# pc2_key.net
KiCad netlist of a schematic drawn in EAGLE
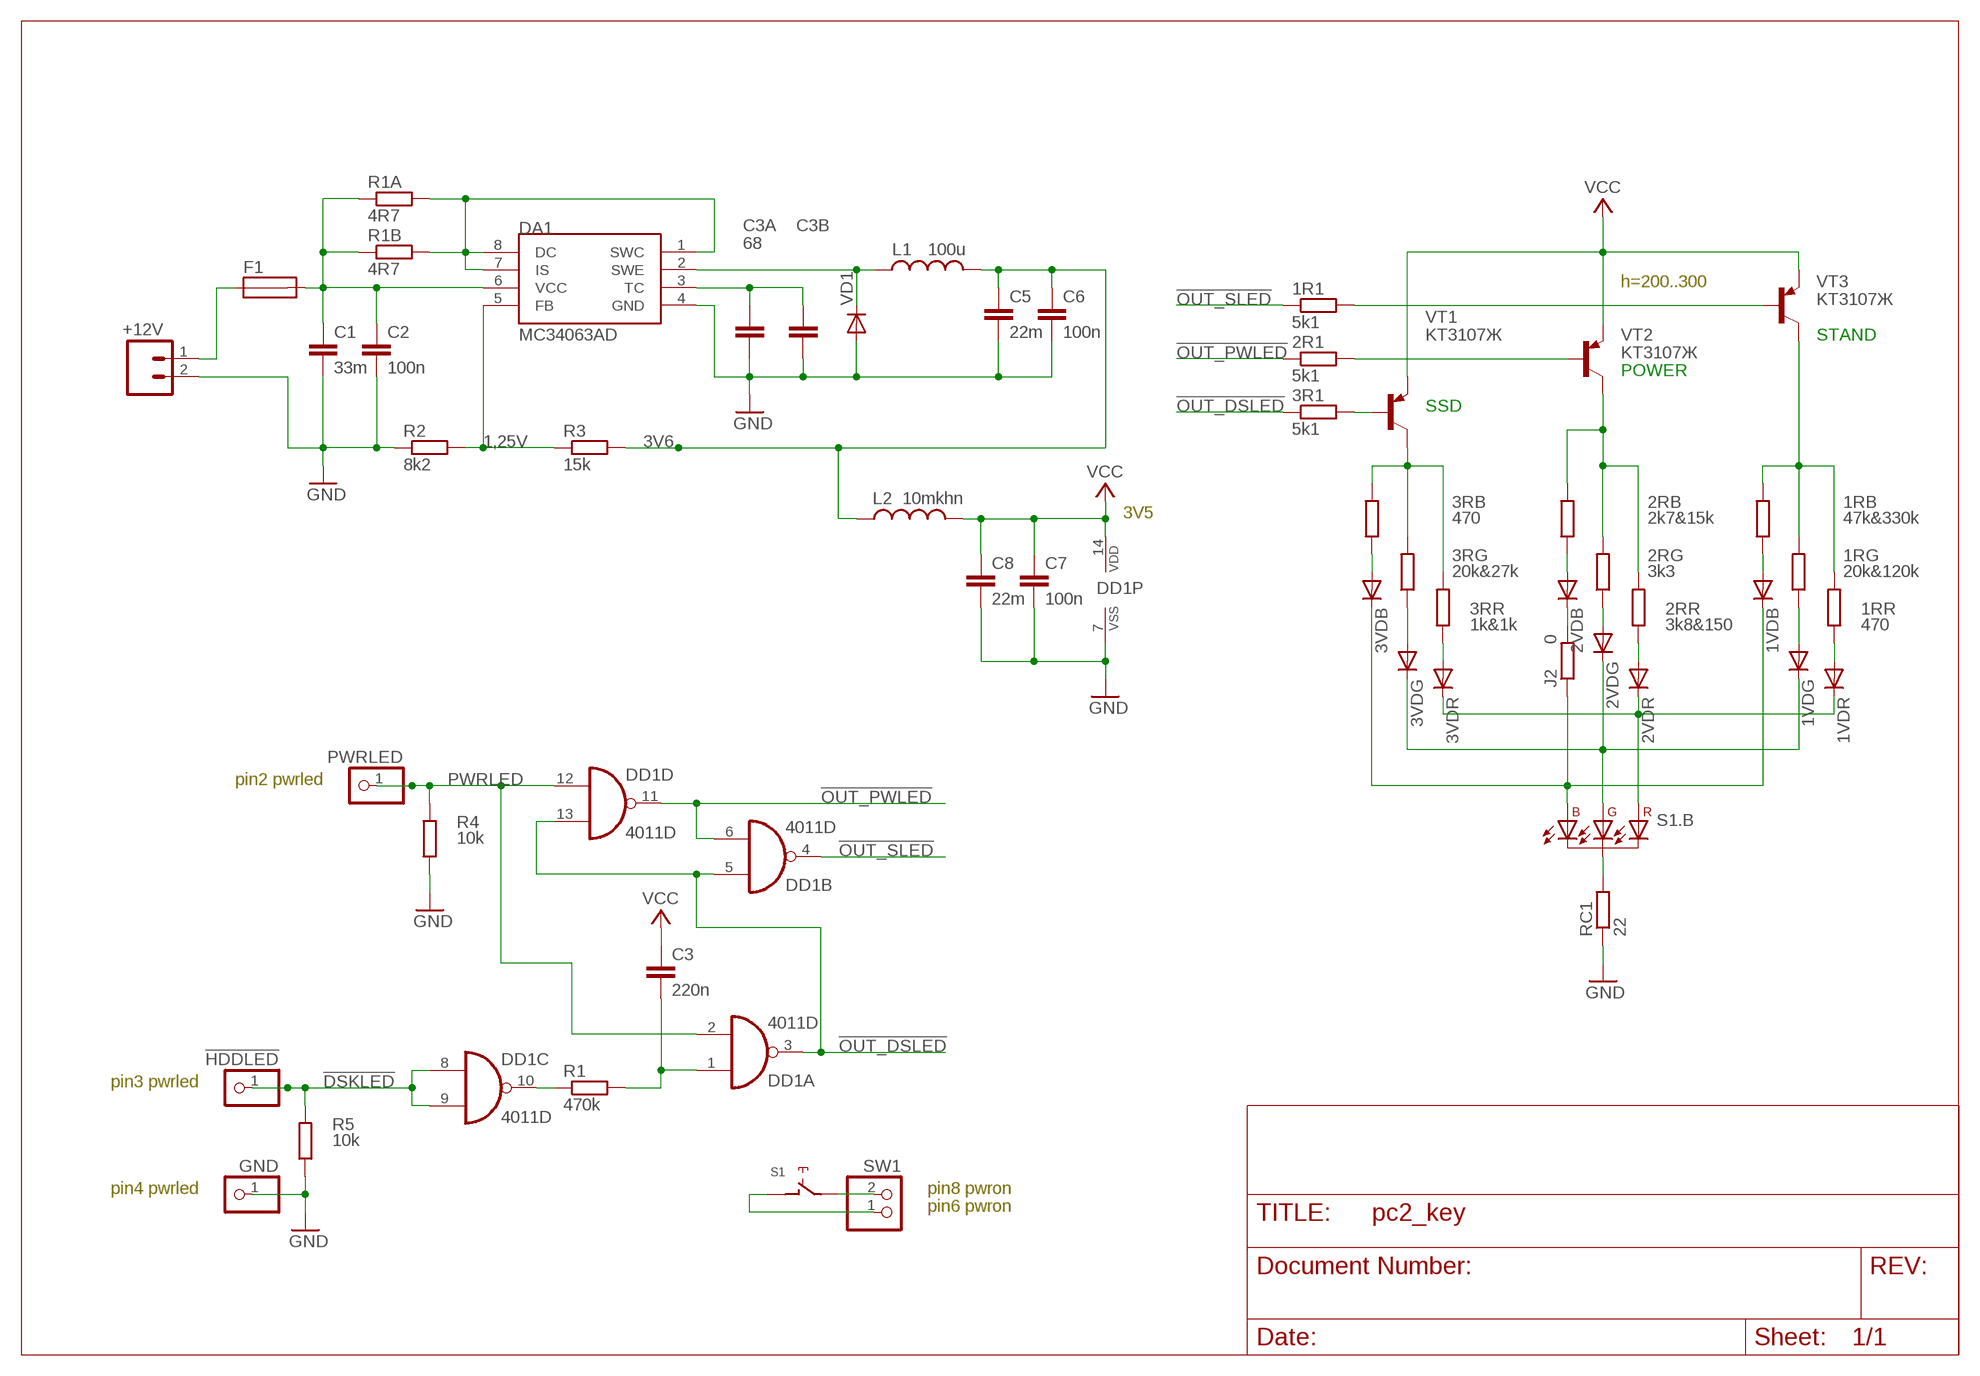
[diagram p0: schematic, sheet 1]

(export (version "E")
  (design (tool "Eeschema 10.0.6"))
  (components
    (comp (ref "!HDDLED")
      (value "PINHD-1X1")
      (footprint "eagle-import:1X01")
      (libsource (lib "eagle-import") (part "PINHD-1X1"))
    )
    (comp (ref "+12V")
      (value "CON_2P")
      (footprint "eagle-import:CON_PWR_2PIN4MM")
      (libsource (lib "eagle-import") (part "CON_2P"))
    )
    (comp (ref "1R1")
      (value "5k1")
      (footprint "eagle-import:R1206W")
      (libsource (lib "eagle-import") (part "R-EU_R1206W"))
    )
    (comp (ref "1RB")
      (value "47k&330k")
      (footprint "eagle-import:R0805")
      (libsource (lib "eagle-import") (part "R-EU_R0805"))
    )
    (comp (ref "1RG")
      (value "20k&120k")
      (footprint "eagle-import:R0805")
      (libsource (lib "eagle-import") (part "R-EU_R0805"))
    )
    (comp (ref "1RR")
      (value "470")
      (footprint "eagle-import:R0805")
      (libsource (lib "eagle-import") (part "R-EU_R0805"))
    )
    (comp (ref "1VDB")
      (value "DIODE-SOD80C")
      (footprint "eagle-import:SOD80C")
      (libsource (lib "eagle-import") (part "DIODE-SOD80C"))
    )
    (comp (ref "1VDG")
      (value "DIODE-SOD80C")
      (footprint "eagle-import:SOD80C")
      (libsource (lib "eagle-import") (part "DIODE-SOD80C"))
    )
    (comp (ref "1VDR")
      (value "DIODE-SOD80C")
      (footprint "eagle-import:SOD80C")
      (libsource (lib "eagle-import") (part "DIODE-SOD80C"))
    )
    (comp (ref "2R1")
      (value "5k1")
      (footprint "eagle-import:R1206W")
      (libsource (lib "eagle-import") (part "R-EU_R1206W"))
    )
    (comp (ref "2RB")
      (value "2k7&15k")
      (footprint "eagle-import:R0805")
      (libsource (lib "eagle-import") (part "R-EU_R0805"))
    )
    (comp (ref "2RG")
      (value "3k3")
      (footprint "eagle-import:R0805")
      (libsource (lib "eagle-import") (part "R-EU_R0805"))
    )
    (comp (ref "2RR")
      (value "3k8&150")
      (footprint "eagle-import:R0805")
      (libsource (lib "eagle-import") (part "R-EU_R0805"))
    )
    (comp (ref "2VDB")
      (value "DIODE-SOD80C")
      (footprint "eagle-import:SOD80C")
      (libsource (lib "eagle-import") (part "DIODE-SOD80C"))
    )
    (comp (ref "2VDG")
      (value "DIODE-SOD80C")
      (footprint "eagle-import:SOD80C")
      (libsource (lib "eagle-import") (part "DIODE-SOD80C"))
    )
    (comp (ref "2VDR")
      (value "DIODE-SOD80C")
      (footprint "eagle-import:SOD80C")
      (libsource (lib "eagle-import") (part "DIODE-SOD80C"))
    )
    (comp (ref "3R1")
      (value "5k1")
      (footprint "eagle-import:R1206W")
      (libsource (lib "eagle-import") (part "R-EU_R1206W"))
    )
    (comp (ref "3RB")
      (value "470")
      (footprint "eagle-import:R0805")
      (libsource (lib "eagle-import") (part "R-EU_R0805"))
    )
    (comp (ref "3RG")
      (value "20k&27k")
      (footprint "eagle-import:R0805")
      (libsource (lib "eagle-import") (part "R-EU_R0805"))
    )
    (comp (ref "3RR")
      (value "1k&1k")
      (footprint "eagle-import:R0805")
      (libsource (lib "eagle-import") (part "R-EU_R0805"))
    )
    (comp (ref "3VDB")
      (value "DIODE-SOD80C")
      (footprint "eagle-import:SOD80C")
      (libsource (lib "eagle-import") (part "DIODE-SOD80C"))
    )
    (comp (ref "3VDG")
      (value "DIODE-SOD80C")
      (footprint "eagle-import:SOD80C")
      (libsource (lib "eagle-import") (part "DIODE-SOD80C"))
    )
    (comp (ref "3VDR")
      (value "DIODE-SOD80C")
      (footprint "eagle-import:SOD80C")
      (libsource (lib "eagle-import") (part "DIODE-SOD80C"))
    )
    (comp (ref "C1")
      (value "33m")
      (footprint "eagle-import:C1210")
      (libsource (lib "eagle-import") (part "C-EUC1210"))
    )
    (comp (ref "C2")
      (value "100n")
      (footprint "eagle-import:C0805K")
      (libsource (lib "eagle-import") (part "resistor_C-EUC0805K"))
    )
    (comp (ref "C3")
      (value "220n")
      (footprint "eagle-import:C0805")
      (libsource (lib "eagle-import") (part "resistor_C-EUC0805"))
    )
    (comp (ref "C3A")
      (value "68")
      (footprint "eagle-import:C0805K")
      (libsource (lib "eagle-import") (part "resistor_C-EUC0805K"))
    )
    (comp (ref "C3B")
      (value "C-EUC0805K")
      (footprint "eagle-import:C0805K")
      (libsource (lib "eagle-import") (part "resistor_C-EUC0805K"))
    )
    (comp (ref "C5")
      (value "22m")
      (footprint "eagle-import:C1210")
      (libsource (lib "eagle-import") (part "C-EUC1210"))
    )
    (comp (ref "C6")
      (value "100n")
      (footprint "eagle-import:C0805K")
      (libsource (lib "eagle-import") (part "resistor_C-EUC0805K"))
    )
    (comp (ref "C7")
      (value "100n")
      (footprint "eagle-import:C0805K")
      (libsource (lib "eagle-import") (part "resistor_C-EUC0805K"))
    )
    (comp (ref "C8")
      (value "22m")
      (footprint "eagle-import:C1210")
      (libsource (lib "eagle-import") (part "C-EUC1210"))
    )
    (comp (ref "DA1")
      (value "MC34063AD")
      (footprint "eagle-import:SOIC8")
      (libsource (lib "eagle-import") (part "MC34063AD"))
    )
    (comp (ref "DD1")
      (value "4011D")
      (footprint "eagle-import:SO14")
      (libsource (lib "eagle-import") (part "4011D"))
    )
    (comp (ref "F1")
      (value "SH32")
      (footprint "eagle-import:SH32")
      (fields (field (name "MPN") "10207101009"))
      (libsource (lib "eagle-import") (part "SH32"))
    )
    (comp (ref "GND")
      (value "PINHD-1X1")
      (footprint "eagle-import:1X01")
      (libsource (lib "eagle-import") (part "PINHD-1X1"))
    )
    (comp (ref "J2")
      (value "0")
      (footprint "eagle-import:R1206W")
      (libsource (lib "eagle-import") (part "R-EU_R1206W"))
    )
    (comp (ref "L1")
      (value "100u")
      (footprint "eagle-import:LH7X10MM")
      (libsource (lib "eagle-import") (part "L_LH7X10MM"))
    )
    (comp (ref "L2")
      (value "10mkhn")
      (footprint "eagle-import:PIS2816")
      (libsource (lib "eagle-import") (part "L-USPIS2816"))
    )
    (comp (ref "PWRLED")
      (value "PINHD-1X1")
      (footprint "eagle-import:1X01")
      (libsource (lib "eagle-import") (part "PINHD-1X1"))
    )
    (comp (ref "R1")
      (value "470k")
      (footprint "eagle-import:M0805")
      (libsource (lib "eagle-import") (part "R-EU_M0805"))
    )
    (comp (ref "R1A")
      (value "4R7")
      (footprint "eagle-import:R1206")
      (libsource (lib "eagle-import") (part "resistor_R-EU_R1206"))
    )
    (comp (ref "R1B")
      (value "4R7")
      (footprint "eagle-import:R1206")
      (libsource (lib "eagle-import") (part "resistor_R-EU_R1206"))
    )
    (comp (ref "R2")
      (value "8k2")
      (footprint "eagle-import:R0805")
      (libsource (lib "eagle-import") (part "resistor_R-EU_R0805"))
    )
    (comp (ref "R3")
      (value "15k")
      (footprint "eagle-import:R0805")
      (libsource (lib "eagle-import") (part "resistor_R-EU_R0805"))
    )
    (comp (ref "R4")
      (value "10k")
      (footprint "eagle-import:M0805")
      (libsource (lib "eagle-import") (part "R-EU_M0805"))
    )
    (comp (ref "R5")
      (value "10k")
      (footprint "eagle-import:R1206W")
      (libsource (lib "eagle-import") (part "R-EU_R1206W"))
    )
    (comp (ref "RC1")
      (value "22")
      (footprint "eagle-import:R0805")
      (libsource (lib "eagle-import") (part "R-EU_R0805"))
    )
    (comp (ref "S1")
      (value "CHERRY-MX")
      (footprint "eagle-import:CHERRY-MX-4P")
      (libsource (lib "eagle-import") (part "CHERRY-MX"))
    )
    (comp (ref "SW1")
      (value "PINHD-1X2")
      (footprint "eagle-import:1X02")
      (libsource (lib "eagle-import") (part "PINHD-1X2"))
    )
    (comp (ref "VD1")
      (value "DIODE-SMB")
      (footprint "eagle-import:SMB")
      (libsource (lib "eagle-import") (part "DIODE-SMB"))
    )
    (comp (ref "VT1")
      (value "KT3107Ж")
      (footprint "eagle-import:TO92")
      (libsource (lib "eagle-import") (part "BJT_PNP_TO-92_EBC"))
    )
    (comp (ref "VT2")
      (value "KT3107Ж")
      (footprint "eagle-import:TO92")
      (libsource (lib "eagle-import") (part "BJT_PNP_TO-92_EBC"))
    )
    (comp (ref "VT3")
      (value "KT3107Ж")
      (footprint "eagle-import:TO92")
      (libsource (lib "eagle-import") (part "BJT_PNP_TO-92_EBC"))
    )
  )
  (nets
    (net (code "1") (name "/1,25V") (class "Default")
      (node (ref "DA1") (pin "5") (pinfunction "FB_5") (pintype "passive"))
      (node (ref "R2") (pin "2") (pinfunction "2_2") (pintype "passive"))
      (node (ref "R3") (pin "1") (pinfunction "1_1") (pintype "passive"))
    )
    (net (code "2") (name "/3V6") (class "Default")
      (node (ref "C5") (pin "1") (pinfunction "1_1") (pintype "passive"))
      (node (ref "C6") (pin "1") (pinfunction "1_1") (pintype "passive"))
      (node (ref "L1") (pin "1") (pinfunction "1_1") (pintype "passive"))
      (node (ref "L2") (pin "1") (pinfunction "1_1") (pintype "passive"))
      (node (ref "R3") (pin "2") (pinfunction "2_2") (pintype "passive"))
    )
    (net (code "3") (name "/PWRLED") (class "Default")
      (node (ref "DD1") (pin "12") (pinfunction "I0_12") (pintype "input"))
      (node (ref "DD1") (pin "2") (pinfunction "I1_2") (pintype "input"))
      (node (ref "PWRLED") (pin "1") (pinfunction "1_1") (pintype "passive"))
      (node (ref "R4") (pin "2") (pinfunction "2_2") (pintype "passive"))
    )
    (net (code "4") (name "/~{DSKLED}") (class "Default")
      (node (ref "!HDDLED") (pin "1") (pinfunction "1_1") (pintype "passive"))
      (node (ref "DD1") (pin "8") (pinfunction "I0_8") (pintype "input"))
      (node (ref "DD1") (pin "9") (pinfunction "I1_9") (pintype "input"))
      (node (ref "R5") (pin "2") (pinfunction "2_2") (pintype "passive"))
    )
    (net (code "5") (name "/~{OUT_DSLED}") (class "Default")
      (node (ref "3R1") (pin "1") (pinfunction "1_1") (pintype "passive"))
      (node (ref "DD1") (pin "13") (pinfunction "I1_13") (pintype "input"))
      (node (ref "DD1") (pin "3") (pinfunction "O_3") (pintype "output"))
      (node (ref "DD1") (pin "5") (pinfunction "I0_5") (pintype "input"))
    )
    (net (code "6") (name "/~{OUT_PWLED}") (class "Default")
      (node (ref "2R1") (pin "1") (pinfunction "1_1") (pintype "passive"))
      (node (ref "DD1") (pin "11") (pinfunction "O_11") (pintype "output"))
      (node (ref "DD1") (pin "6") (pinfunction "I1_6") (pintype "input"))
    )
    (net (code "7") (name "/~{OUT_SLED}") (class "Default")
      (node (ref "1R1") (pin "1") (pinfunction "1_1") (pintype "passive"))
      (node (ref "DD1") (pin "4") (pinfunction "O_4") (pintype "output"))
    )
    (net (code "8") (name "GND") (class "Default")
      (node (ref "+12V") (pin "2") (pinfunction "2_2") (pintype "passive"))
      (node (ref "C1") (pin "2") (pinfunction "2_2") (pintype "passive"))
      (node (ref "C2") (pin "2") (pinfunction "2_2") (pintype "passive"))
      (node (ref "C3A") (pin "2") (pinfunction "2_2") (pintype "passive"))
      (node (ref "C3B") (pin "2") (pinfunction "2_2") (pintype "passive"))
      (node (ref "C5") (pin "2") (pinfunction "2_2") (pintype "passive"))
      (node (ref "C6") (pin "2") (pinfunction "2_2") (pintype "passive"))
      (node (ref "C7") (pin "2") (pinfunction "2_2") (pintype "passive"))
      (node (ref "C8") (pin "2") (pinfunction "2_2") (pintype "passive"))
      (node (ref "DA1") (pin "4") (pinfunction "GND_4") (pintype "passive"))
      (node (ref "DD1") (pin "7") (pinfunction "VSS_7") (pintype "power_in"))
      (node (ref "GND") (pin "1") (pinfunction "1_1") (pintype "passive"))
      (node (ref "R2") (pin "1") (pinfunction "1_1") (pintype "passive"))
      (node (ref "R4") (pin "1") (pinfunction "1_1") (pintype "passive"))
      (node (ref "R5") (pin "1") (pinfunction "1_1") (pintype "passive"))
      (node (ref "RC1") (pin "1") (pinfunction "1_1") (pintype "passive"))
      (node (ref "VD1") (pin "A") (pinfunction "A_A") (pintype "passive"))
    )
    (net (code "9") (name "Net-(1RB-Pad1)") (class "Default")
      (node (ref "1RB") (pin "1") (pinfunction "1_1") (pintype "passive"))
      (node (ref "1VDB") (pin "A") (pinfunction "A_A") (pintype "passive"))
    )
    (net (code "10") (name "Net-(1RG-Pad1)") (class "Default")
      (node (ref "1RG") (pin "1") (pinfunction "1_1") (pintype "passive"))
      (node (ref "1VDG") (pin "A") (pinfunction "A_A") (pintype "passive"))
    )
    (net (code "11") (name "Net-(1RR-Pad1)") (class "Default")
      (node (ref "1RR") (pin "1") (pinfunction "1_1") (pintype "passive"))
      (node (ref "1VDR") (pin "A") (pinfunction "A_A") (pintype "passive"))
    )
    (net (code "12") (name "Net-(2RB-Pad1)") (class "Default")
      (node (ref "2RB") (pin "1") (pinfunction "1_1") (pintype "passive"))
      (node (ref "2VDB") (pin "A") (pinfunction "A_A") (pintype "passive"))
    )
    (net (code "13") (name "Net-(2RG-Pad1)") (class "Default")
      (node (ref "2RG") (pin "1") (pinfunction "1_1") (pintype "passive"))
      (node (ref "2VDG") (pin "A") (pinfunction "A_A") (pintype "passive"))
    )
    (net (code "14") (name "Net-(2RR-Pad1)") (class "Default")
      (node (ref "2RR") (pin "1") (pinfunction "1_1") (pintype "passive"))
      (node (ref "2VDR") (pin "A") (pinfunction "A_A") (pintype "passive"))
    )
    (net (code "15") (name "Net-(2VDB-PadC)") (class "Default")
      (node (ref "2VDB") (pin "C") (pinfunction "C_C") (pintype "passive"))
      (node (ref "J2") (pin "2") (pinfunction "2_2") (pintype "passive"))
    )
    (net (code "16") (name "Net-(3RB-Pad1)") (class "Default")
      (node (ref "3RB") (pin "1") (pinfunction "1_1") (pintype "passive"))
      (node (ref "3VDB") (pin "A") (pinfunction "A_A") (pintype "passive"))
    )
    (net (code "17") (name "Net-(3RG-Pad1)") (class "Default")
      (node (ref "3RG") (pin "1") (pinfunction "1_1") (pintype "passive"))
      (node (ref "3VDG") (pin "A") (pinfunction "A_A") (pintype "passive"))
    )
    (net (code "18") (name "Net-(3RR-Pad1)") (class "Default")
      (node (ref "3RR") (pin "1") (pinfunction "1_1") (pintype "passive"))
      (node (ref "3VDR") (pin "A") (pinfunction "A_A") (pintype "passive"))
    )
    (net (code "19") (name "Net-(DA1-DC)") (class "Default")
      (node (ref "DA1") (pin "1") (pinfunction "SWC_1") (pintype "passive"))
      (node (ref "DA1") (pin "7") (pinfunction "IS_7") (pintype "passive"))
      (node (ref "DA1") (pin "8") (pinfunction "DC_8") (pintype "passive"))
      (node (ref "R1A") (pin "2") (pinfunction "2_2") (pintype "passive"))
      (node (ref "R1B") (pin "2") (pinfunction "2_2") (pintype "passive"))
    )
    (net (code "20") (name "Net-(DA1-SWE)") (class "Default")
      (node (ref "DA1") (pin "2") (pinfunction "SWE_2") (pintype "passive"))
      (node (ref "L1") (pin "2") (pinfunction "2_2") (pintype "passive"))
      (node (ref "VD1") (pin "C") (pinfunction "C_C") (pintype "passive"))
    )
    (net (code "21") (name "Net-(DA1-TC)") (class "Default")
      (node (ref "C3A") (pin "1") (pinfunction "1_1") (pintype "passive"))
      (node (ref "C3B") (pin "1") (pinfunction "1_1") (pintype "passive"))
      (node (ref "DA1") (pin "3") (pinfunction "TC_3") (pintype "passive"))
    )
    (net (code "22") (name "Net-(DA1-VCC)") (class "Default")
      (node (ref "C1") (pin "1") (pinfunction "1_1") (pintype "passive"))
      (node (ref "C2") (pin "1") (pinfunction "1_1") (pintype "passive"))
      (node (ref "DA1") (pin "6") (pinfunction "VCC_6") (pintype "passive"))
      (node (ref "F1") (pin "P$2") (pinfunction "2A_P$2") (pintype "passive"))
      (node (ref "R1A") (pin "1") (pinfunction "1_1") (pintype "passive"))
      (node (ref "R1B") (pin "1") (pinfunction "1_1") (pintype "passive"))
    )
    (net (code "23") (name "Net-(DD1A-I0)") (class "Default")
      (node (ref "C3") (pin "2") (pinfunction "2_2") (pintype "passive"))
      (node (ref "DD1") (pin "1") (pinfunction "I0_1") (pintype "input"))
      (node (ref "R1") (pin "2") (pinfunction "2_2") (pintype "passive"))
    )
    (net (code "24") (name "Net-(DD1C-O)") (class "Default")
      (node (ref "DD1") (pin "10") (pinfunction "O_10") (pintype "output"))
      (node (ref "R1") (pin "1") (pinfunction "1_1") (pintype "passive"))
    )
    (net (code "25") (name "Net-(F1-1A)") (class "Default")
      (node (ref "+12V") (pin "1") (pinfunction "1_1") (pintype "passive"))
      (node (ref "F1") (pin "P$1") (pinfunction "1A_P$1") (pintype "passive"))
    )
    (net (code "26") (name "Net-(S1-PadSW1)") (class "Default")
      (node (ref "S1") (pin "SW1") (pinfunction "SW1_SW1") (pintype "passive"))
      (node (ref "SW1") (pin "2") (pinfunction "2_2") (pintype "passive"))
    )
    (net (code "27") (name "Net-(S1-PadSW2)") (class "Default")
      (node (ref "S1") (pin "SW2") (pinfunction "SW2_SW2") (pintype "passive"))
      (node (ref "SW1") (pin "1") (pinfunction "1_1") (pintype "passive"))
    )
    (net (code "28") (name "Net-(S1B-B)") (class "Default")
      (node (ref "1VDB") (pin "C") (pinfunction "C_C") (pintype "passive"))
      (node (ref "3VDB") (pin "C") (pinfunction "C_C") (pintype "passive"))
      (node (ref "J2") (pin "1") (pinfunction "1_1") (pintype "passive"))
      (node (ref "S1") (pin "D1") (pinfunction "B_D1") (pintype "passive"))
    )
    (net (code "29") (name "Net-(S1B-G)") (class "Default")
      (node (ref "1VDG") (pin "C") (pinfunction "C_C") (pintype "passive"))
      (node (ref "2VDG") (pin "C") (pinfunction "C_C") (pintype "passive"))
      (node (ref "3VDG") (pin "C") (pinfunction "C_C") (pintype "passive"))
      (node (ref "S1") (pin "D2") (pinfunction "G_D2") (pintype "passive"))
    )
    (net (code "30") (name "Net-(S1B-R)") (class "Default")
      (node (ref "1VDR") (pin "C") (pinfunction "C_C") (pintype "passive"))
      (node (ref "2VDR") (pin "C") (pinfunction "C_C") (pintype "passive"))
      (node (ref "3VDR") (pin "C") (pinfunction "C_C") (pintype "passive"))
      (node (ref "S1") (pin "D4") (pinfunction "R_D4") (pintype "passive"))
    )
    (net (code "31") (name "Net-(S1B-RGB-)") (class "Default")
      (node (ref "RC1") (pin "2") (pinfunction "2_2") (pintype "passive"))
      (node (ref "S1") (pin "D3") (pinfunction "RGB-_D3") (pintype "bidirectional"))
    )
    (net (code "32") (name "Net-(VT1-B)") (class "Default")
      (node (ref "3R1") (pin "2") (pinfunction "2_2") (pintype "passive"))
      (node (ref "VT1") (pin "2") (pinfunction "B_2") (pintype "passive"))
    )
    (net (code "33") (name "Net-(VT1-C)") (class "Default")
      (node (ref "3RB") (pin "2") (pinfunction "2_2") (pintype "passive"))
      (node (ref "3RG") (pin "2") (pinfunction "2_2") (pintype "passive"))
      (node (ref "3RR") (pin "2") (pinfunction "2_2") (pintype "passive"))
      (node (ref "VT1") (pin "3") (pinfunction "C_3") (pintype "passive"))
    )
    (net (code "34") (name "Net-(VT2-B)") (class "Default")
      (node (ref "2R1") (pin "2") (pinfunction "2_2") (pintype "passive"))
      (node (ref "VT2") (pin "2") (pinfunction "B_2") (pintype "passive"))
    )
    (net (code "35") (name "Net-(VT2-C)") (class "Default")
      (node (ref "2RB") (pin "2") (pinfunction "2_2") (pintype "passive"))
      (node (ref "2RG") (pin "2") (pinfunction "2_2") (pintype "passive"))
      (node (ref "2RR") (pin "2") (pinfunction "2_2") (pintype "passive"))
      (node (ref "VT2") (pin "3") (pinfunction "C_3") (pintype "passive"))
    )
    (net (code "36") (name "Net-(VT3-B)") (class "Default")
      (node (ref "1R1") (pin "2") (pinfunction "2_2") (pintype "passive"))
      (node (ref "VT3") (pin "2") (pinfunction "B_2") (pintype "passive"))
    )
    (net (code "37") (name "Net-(VT3-C)") (class "Default")
      (node (ref "1RB") (pin "2") (pinfunction "2_2") (pintype "passive"))
      (node (ref "1RG") (pin "2") (pinfunction "2_2") (pintype "passive"))
      (node (ref "1RR") (pin "2") (pinfunction "2_2") (pintype "passive"))
      (node (ref "VT3") (pin "3") (pinfunction "C_3") (pintype "passive"))
    )
    (net (code "38") (name "VCC") (class "Default")
      (node (ref "C3") (pin "1") (pinfunction "1_1") (pintype "passive"))
      (node (ref "C7") (pin "1") (pinfunction "1_1") (pintype "passive"))
      (node (ref "C8") (pin "1") (pinfunction "1_1") (pintype "passive"))
      (node (ref "DD1") (pin "14") (pinfunction "VDD_14") (pintype "power_in"))
      (node (ref "L2") (pin "2") (pinfunction "2_2") (pintype "passive"))
      (node (ref "VT1") (pin "1") (pinfunction "E_1") (pintype "passive"))
      (node (ref "VT2") (pin "1") (pinfunction "E_1") (pintype "passive"))
      (node (ref "VT3") (pin "1") (pinfunction "E_1") (pintype "passive"))
    )
  )
)
